# reefpi_pico_ph.net
KiCad netlist of a schematic drawn in Altium Designer
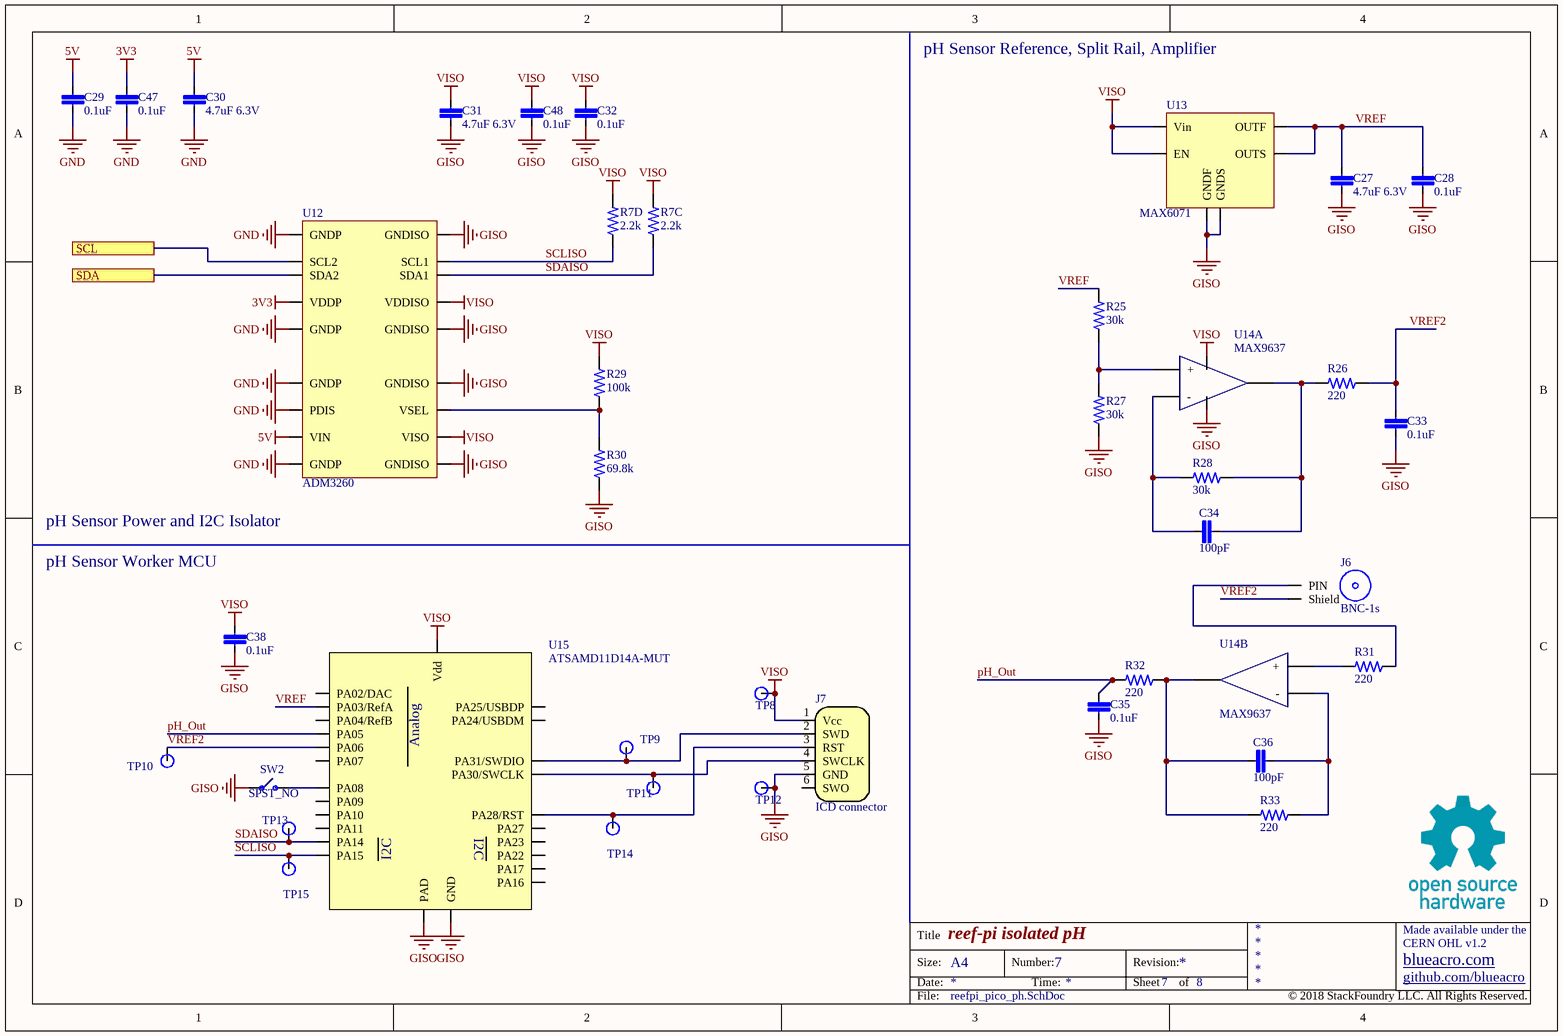
[diagram p0: reefpi_pico_ph.SchDoc]

(export (version "E")
  (design (tool "Eeschema 10.0.6"))
  (components
    (comp (ref "C27") (value "4.7uF 6.3V") (footprint "C0603") (libsource (lib "rcl") (part "C-EU")))
    (comp (ref "C28") (value "0.1uF") (footprint "C0603") (libsource (lib "rcl") (part "C-EU")))
    (comp (ref "C29") (value "0.1uF") (footprint "C0603") (libsource (lib "rcl") (part "C-EU")))
    (comp (ref "C30") (value "4.7uF 6.3V") (footprint "C0603") (libsource (lib "rcl") (part "C-EU")))
    (comp (ref "C31") (value "4.7uF 6.3V") (footprint "C0603") (libsource (lib "rcl") (part "C-EU")))
    (comp (ref "C32") (value "0.1uF") (footprint "C0603") (libsource (lib "rcl") (part "C-EU")))
    (comp (ref "C33") (value "0.1uF") (footprint "C0603") (libsource (lib "rcl") (part "C-EU")))
    (comp (ref "C34") (value "100pF") (footprint "C0603") (libsource (lib "") (part "C-EU_1")))
    (comp (ref "C35") (value "0.1uF") (footprint "C0603") (libsource (lib "rcl") (part "C-EU")))
    (comp (ref "C36") (value "100pF") (footprint "C0603") (libsource (lib "") (part "C-EU_1")))
    (comp (ref "C38") (value "0.1uF") (footprint "C0603") (libsource (lib "rcl") (part "C-EU")))
    (comp (ref "C47") (value "0.1uF") (footprint "C0603") (libsource (lib "rcl") (part "C-EU")))
    (comp (ref "C48") (value "0.1uF") (footprint "C0603") (libsource (lib "rcl") (part "C-EU")))
    (comp (ref "J6")
      (value "BNC-1s")
      (footprint "31-5431-10RFX")
      (libsource (lib "connectors") (part "BNC-1s"))
    )
    (comp (ref "J7")
      (value "ICD connector")
      (footprint "TC2030-MCP-NL")
      (description "Conector par ICD")
      (libsource (lib "TC2030") (part "TC2030-SWD-NL"))
    )
    (comp (ref "R7") (value "2.2k") (footprint "R0603x4") (libsource (lib "rcl") (part "R-US-4ch")))
    (comp (ref "R25") (value "30k") (footprint "R0603") (libsource (lib "rcl") (part "R-US")))
    (comp (ref "R26") (value "220") (footprint "R0603") (libsource (lib "rcl") (part "R-US")))
    (comp (ref "R27") (value "30k") (footprint "R0603") (libsource (lib "rcl") (part "R-US")))
    (comp (ref "R28") (value "30k") (footprint "R0603") (libsource (lib "rcl") (part "R-US")))
    (comp (ref "R29") (value "100k") (footprint "R0603") (libsource (lib "rcl") (part "R-US")))
    (comp (ref "R30") (value "69.8k") (footprint "R0603") (libsource (lib "rcl") (part "R-US")))
    (comp (ref "R31") (value "220") (footprint "R0603") (libsource (lib "rcl") (part "R-US")))
    (comp (ref "R32") (value "220") (footprint "R0603") (libsource (lib "rcl") (part "R-US")))
    (comp (ref "R33") (value "220") (footprint "R0603") (libsource (lib "rcl") (part "R-US")))
    (comp (ref "SW2") (value "SPST_NO") (footprint "B3U-1000P") (libsource (lib "switches") (part "SPST_NO")))
    (comp (ref "TP8") (value "TP") (footprint "TP_0.89mm") (libsource (lib "testpoints") (part "TP")))
    (comp (ref "TP9") (value "TP") (footprint "TP_0.89mm") (libsource (lib "testpoints") (part "TP")))
    (comp (ref "TP10") (value "TP") (footprint "TP_0.89mm") (libsource (lib "testpoints") (part "TP")))
    (comp (ref "TP11") (value "TP") (footprint "TP_0.89mm") (libsource (lib "testpoints") (part "TP")))
    (comp (ref "TP12") (value "TP") (footprint "TP_0.89mm") (libsource (lib "testpoints") (part "TP")))
    (comp (ref "TP13") (value "TP") (footprint "TP_0.89mm") (libsource (lib "testpoints") (part "TP")))
    (comp (ref "TP14") (value "TP") (footprint "TP_0.89mm") (libsource (lib "testpoints") (part "TP")))
    (comp (ref "TP15") (value "TP") (footprint "TP_0.89mm") (libsource (lib "testpoints") (part "TP")))
    (comp (ref "U12")
      (value "ADM3260")
      (footprint "SSOP20")
      (libsource (lib "analog_devices") (part "ADM3260"))
    )
    (comp (ref "U13") (value "MAX6071") (footprint "SOT23-6L") (libsource (lib "maxim") (part "MAX6071")))
    (comp (ref "U14") (value "MAX9637") (footprint "SC70-8") (libsource (lib "maxim") (part "MAX9637")))
    (comp (ref "U15")
      (value "ATSAMD11D14A-MUT")
      (footprint "QFN24-4x4mm-0.5")
      (libsource (lib "atmel") (part "ATSAMD11D14A-MUT"))
    )
  )
  (nets
    (net (code "1") (name "/SCL") (class "Default")
      (node (ref "U12") (pin "2") (pinfunction "SCL2_2") (pintype "passive"))
    )
    (net (code "2") (name "/SCLISO") (class "Default")
      (node (ref "R7") (pin "7") (pinfunction "7_7") (pintype "passive"))
      (node (ref "TP15") (pin "1") (pinfunction "1_1") (pintype "passive"))
      (node (ref "U12") (pin "19") (pinfunction "SCL1_19") (pintype "passive"))
      (node (ref "U15") (pin "12") (pinfunction "PA15_12") (pintype "passive"))
    )
    (net (code "3") (name "/SDA") (class "Default")
      (node (ref "U12") (pin "3") (pinfunction "SDA2_3") (pintype "passive"))
    )
    (net (code "4") (name "/SDAISO") (class "Default")
      (node (ref "R7") (pin "5") (pinfunction "5_5") (pintype "passive"))
      (node (ref "TP13") (pin "1") (pinfunction "1_1") (pintype "passive"))
      (node (ref "U12") (pin "18") (pinfunction "SDA1_18") (pintype "passive"))
      (node (ref "U15") (pin "11") (pinfunction "PA14_11") (pintype "passive"))
    )
    (net (code "5") (name "/VREF") (class "Default")
      (node (ref "C27") (pin "1") (pinfunction "1_1") (pintype "passive"))
      (node (ref "C28") (pin "1") (pinfunction "1_1") (pintype "passive"))
      (node (ref "R25") (pin "2") (pinfunction "2_2") (pintype "passive"))
      (node (ref "U13") (pin "5") (pinfunction "OUTS_5") (pintype "passive"))
      (node (ref "U13") (pin "6") (pinfunction "OUTF_6") (pintype "passive"))
      (node (ref "U15") (pin "2") (pinfunction "PA03/RefA_2") (pintype "passive"))
    )
    (net (code "6") (name "/VREF2") (class "Default")
      (node (ref "C33") (pin "1") (pinfunction "1_1") (pintype "passive"))
      (node (ref "J6") (pin "SHIELD") (pinfunction "Shield_SHIELD") (pintype "passive"))
      (node (ref "R26") (pin "1") (pinfunction "1_1") (pintype "passive"))
      (node (ref "TP10") (pin "1") (pinfunction "1_1") (pintype "passive"))
      (node (ref "U15") (pin "5") (pinfunction "PA06_5") (pintype "passive"))
    )
    (net (code "7") (name "/pH_Out") (class "Default")
      (node (ref "C35") (pin "1") (pinfunction "1_1") (pintype "passive"))
      (node (ref "R32") (pin "2") (pinfunction "2_2") (pintype "passive"))
      (node (ref "U15") (pin "4") (pinfunction "PA05_4") (pintype "passive"))
    )
    (net (code "8") (name "3V3") (class "Default")
      (node (ref "C47") (pin "1") (pinfunction "1_1") (pintype "passive"))
      (node (ref "U12") (pin "4") (pinfunction "VDDP_4") (pintype "passive"))
    )
    (net (code "9") (name "5V") (class "Default")
      (node (ref "C29") (pin "1") (pinfunction "1_1") (pintype "passive"))
      (node (ref "C30") (pin "1") (pinfunction "1_1") (pintype "passive"))
      (node (ref "U12") (pin "9") (pinfunction "VIN_9") (pintype "passive"))
    )
    (net (code "10") (name "GISO") (class "Default")
      (node (ref "C27") (pin "2") (pinfunction "2_2") (pintype "passive"))
      (node (ref "C28") (pin "2") (pinfunction "2_2") (pintype "passive"))
      (node (ref "C31") (pin "2") (pinfunction "2_2") (pintype "passive"))
      (node (ref "C32") (pin "2") (pinfunction "2_2") (pintype "passive"))
      (node (ref "C33") (pin "2") (pinfunction "2_2") (pintype "passive"))
      (node (ref "C35") (pin "2") (pinfunction "2_2") (pintype "passive"))
      (node (ref "C38") (pin "2") (pinfunction "2_2") (pintype "passive"))
      (node (ref "C48") (pin "2") (pinfunction "2_2") (pintype "passive"))
      (node (ref "J7") (pin "5") (pinfunction "GND_5") (pintype "passive"))
      (node (ref "R27") (pin "1") (pinfunction "1_1") (pintype "passive"))
      (node (ref "R30") (pin "1") (pinfunction "1_1") (pintype "passive"))
      (node (ref "SW2") (pin "2") (pinfunction "2_2") (pintype "passive"))
      (node (ref "TP12") (pin "1") (pinfunction "1_1") (pintype "passive"))
      (node (ref "U12") (pin "11") (pinfunction "GNDISO_11") (pintype "passive"))
      (node (ref "U12") (pin "14") (pinfunction "GNDISO_14") (pintype "passive"))
      (node (ref "U12") (pin "16") (pinfunction "GNDISO_16") (pintype "passive"))
      (node (ref "U12") (pin "20") (pinfunction "GNDISO_20") (pintype "passive"))
      (node (ref "U13") (pin "1") (pinfunction "GNDF_1") (pintype "passive"))
      (node (ref "U13") (pin "2") (pinfunction "GNDS_2") (pintype "passive"))
      (node (ref "U14") (pin "4") (pintype "passive"))
      (node (ref "U15") (pin "23") (pinfunction "GND_23") (pintype "power_in"))
      (node (ref "U15") (pin "PAD") (pinfunction "PAD_PAD") (pintype "power_in"))
    )
    (net (code "11") (name "GND") (class "Default")
      (node (ref "C29") (pin "2") (pinfunction "2_2") (pintype "passive"))
      (node (ref "C30") (pin "2") (pinfunction "2_2") (pintype "passive"))
      (node (ref "C47") (pin "2") (pinfunction "2_2") (pintype "passive"))
      (node (ref "U12") (pin "1") (pinfunction "GNDP_1") (pintype "passive"))
      (node (ref "U12") (pin "10") (pinfunction "GNDP_10") (pintype "passive"))
      (node (ref "U12") (pin "5") (pinfunction "GNDP_5") (pintype "passive"))
      (node (ref "U12") (pin "7") (pinfunction "GNDP_7") (pintype "passive"))
      (node (ref "U12") (pin "8") (pinfunction "PDIS_8") (pintype "passive"))
    )
    (net (code "12") (name "Net-(J6-PadPIN)") (class "Default")
      (node (ref "J6") (pin "PIN") (pinfunction "PIN_PIN") (pintype "passive"))
      (node (ref "R31") (pin "1") (pinfunction "1_1") (pintype "passive"))
    )
    (net (code "13") (name "Net-(J7-RST)") (class "Default")
      (node (ref "J7") (pin "3") (pinfunction "RST_3") (pintype "passive"))
      (node (ref "TP14") (pin "1") (pinfunction "1_1") (pintype "passive"))
      (node (ref "U15") (pin "18") (pinfunction "PA28/RST_18") (pintype "passive"))
    )
    (net (code "14") (name "Net-(J7-SWCLK)") (class "Default")
      (node (ref "J7") (pin "4") (pinfunction "SWCLK_4") (pintype "passive"))
      (node (ref "TP11") (pin "1") (pinfunction "1_1") (pintype "passive"))
      (node (ref "U15") (pin "19") (pinfunction "PA30/SWCLK_19") (pintype "passive"))
    )
    (net (code "15") (name "Net-(J7-SWD)") (class "Default")
      (node (ref "J7") (pin "2") (pinfunction "SWD_2") (pintype "passive"))
      (node (ref "TP9") (pin "1") (pinfunction "1_1") (pintype "passive"))
      (node (ref "U15") (pin "20") (pinfunction "PA31/SWDIO_20") (pintype "passive"))
    )
    (net (code "16") (name "Net-(U12-VSEL)") (class "Default")
      (node (ref "R29") (pin "1") (pinfunction "1_1") (pintype "passive"))
      (node (ref "R30") (pin "2") (pinfunction "2_2") (pintype "passive"))
      (node (ref "U12") (pin "13") (pinfunction "VSEL_13") (pintype "passive"))
    )
    (net (code "17") (name "Net-(U14A-+)") (class "Default")
      (node (ref "R25") (pin "1") (pinfunction "1_1") (pintype "passive"))
      (node (ref "R27") (pin "2") (pinfunction "2_2") (pintype "passive"))
      (node (ref "U14") (pin "3") (pinfunction "+_3") (pintype "passive"))
    )
    (net (code "18") (name "Net-(U14A--)") (class "Default")
      (node (ref "C34") (pin "1") (pinfunction "1_1") (pintype "passive"))
      (node (ref "R28") (pin "2") (pinfunction "2_2") (pintype "passive"))
      (node (ref "U14") (pin "2") (pinfunction "-_2") (pintype "passive"))
    )
    (net (code "19") (name "Net-(U14A-OUT)") (class "Default")
      (node (ref "C34") (pin "2") (pinfunction "2_2") (pintype "passive"))
      (node (ref "R26") (pin "2") (pinfunction "2_2") (pintype "passive"))
      (node (ref "R28") (pin "1") (pinfunction "1_1") (pintype "passive"))
      (node (ref "U14") (pin "1") (pinfunction "OUT_1") (pintype "passive"))
    )
    (net (code "20") (name "Net-(U14B-+)") (class "Default")
      (node (ref "R31") (pin "2") (pinfunction "2_2") (pintype "passive"))
      (node (ref "U14") (pin "5") (pinfunction "+_5") (pintype "passive"))
    )
    (net (code "21") (name "Net-(U14B--)") (class "Default")
      (node (ref "C36") (pin "2") (pinfunction "2_2") (pintype "passive"))
      (node (ref "R33") (pin "1") (pinfunction "1_1") (pintype "passive"))
      (node (ref "U14") (pin "6") (pinfunction "-_6") (pintype "passive"))
    )
    (net (code "22") (name "Net-(U14B-OUT)") (class "Default")
      (node (ref "C36") (pin "1") (pinfunction "1_1") (pintype "passive"))
      (node (ref "R32") (pin "1") (pinfunction "1_1") (pintype "passive"))
      (node (ref "R33") (pin "2") (pinfunction "2_2") (pintype "passive"))
      (node (ref "U14") (pin "7") (pinfunction "OUT_7") (pintype "passive"))
    )
    (net (code "23") (name "Net-(U15-PA08)") (class "Default")
      (node (ref "SW2") (pin "1") (pinfunction "1_1") (pintype "passive"))
      (node (ref "U15") (pin "7") (pinfunction "PA08_7") (pintype "passive"))
    )
    (net (code "24") (name "VISO") (class "Default")
      (node (ref "C31") (pin "1") (pinfunction "1_1") (pintype "passive"))
      (node (ref "C32") (pin "1") (pinfunction "1_1") (pintype "passive"))
      (node (ref "C38") (pin "1") (pinfunction "1_1") (pintype "passive"))
      (node (ref "C48") (pin "1") (pinfunction "1_1") (pintype "passive"))
      (node (ref "J7") (pin "1") (pinfunction "Vcc_1") (pintype "passive"))
      (node (ref "R29") (pin "2") (pinfunction "2_2") (pintype "passive"))
      (node (ref "R7") (pin "6") (pinfunction "6_6") (pintype "passive"))
      (node (ref "R7") (pin "8") (pinfunction "8_8") (pintype "passive"))
      (node (ref "TP8") (pin "1") (pinfunction "1_1") (pintype "passive"))
      (node (ref "U12") (pin "12") (pinfunction "VISO_12") (pintype "passive"))
      (node (ref "U12") (pin "17") (pinfunction "VDDISO_17") (pintype "passive"))
      (node (ref "U13") (pin "3") (pinfunction "EN_3") (pintype "passive"))
      (node (ref "U13") (pin "4") (pinfunction "Vin_4") (pintype "passive"))
      (node (ref "U14") (pin "8") (pintype "passive"))
      (node (ref "U15") (pin "24") (pinfunction "Vdd_24") (pintype "power_in"))
    )
    (net (code "25") (name "unconnected-(J7-SWO-Pad6)") (class "Default")
      (node (ref "J7") (pin "6") (pinfunction "SWO_6") (pintype "passive"))
    )
    (net (code "26") (name "unconnected-(U15-PA02{slash}DAC-Pad1)") (class "Default")
      (node (ref "U15") (pin "1") (pinfunction "PA02/DAC_1") (pintype "passive"))
    )
    (net (code "27") (name "unconnected-(U15-PA04{slash}RefB-Pad3)") (class "Default")
      (node (ref "U15") (pin "3") (pinfunction "PA04/RefB_3") (pintype "passive"))
    )
    (net (code "28") (name "unconnected-(U15-PA07-Pad6)") (class "Default")
      (node (ref "U15") (pin "6") (pinfunction "PA07_6") (pintype "passive"))
    )
    (net (code "29") (name "unconnected-(U15-PA09-Pad8)") (class "Default")
      (node (ref "U15") (pin "8") (pinfunction "PA09_8") (pintype "passive"))
    )
    (net (code "30") (name "unconnected-(U15-PA10-Pad9)") (class "Default")
      (node (ref "U15") (pin "9") (pinfunction "PA10_9") (pintype "passive"))
    )
    (net (code "31") (name "unconnected-(U15-PA11-Pad10)") (class "Default")
      (node (ref "U15") (pin "10") (pinfunction "PA11_10") (pintype "passive"))
    )
    (net (code "32") (name "unconnected-(U15-PA16-Pad13)") (class "Default")
      (node (ref "U15") (pin "13") (pinfunction "PA16_13") (pintype "passive"))
    )
    (net (code "33") (name "unconnected-(U15-PA17-Pad14)") (class "Default")
      (node (ref "U15") (pin "14") (pinfunction "PA17_14") (pintype "passive"))
    )
    (net (code "34") (name "unconnected-(U15-PA22-Pad15)") (class "Default")
      (node (ref "U15") (pin "15") (pinfunction "PA22_15") (pintype "passive"))
    )
    (net (code "35") (name "unconnected-(U15-PA23-Pad16)") (class "Default")
      (node (ref "U15") (pin "16") (pinfunction "PA23_16") (pintype "passive"))
    )
    (net (code "36") (name "unconnected-(U15-PA24{slash}USBDM-Pad21)") (class "Default")
      (node (ref "U15") (pin "21") (pinfunction "PA24/USBDM_21") (pintype "passive"))
    )
    (net (code "37") (name "unconnected-(U15-PA25{slash}USBDP-Pad22)") (class "Default")
      (node (ref "U15") (pin "22") (pinfunction "PA25/USBDP_22") (pintype "passive"))
    )
    (net (code "38") (name "unconnected-(U15-PA27-Pad17)") (class "Default")
      (node (ref "U15") (pin "17") (pinfunction "PA27_17") (pintype "passive"))
    )
  )
)
